# MCU.net
KiCad netlist of a schematic drawn in Altium Designer
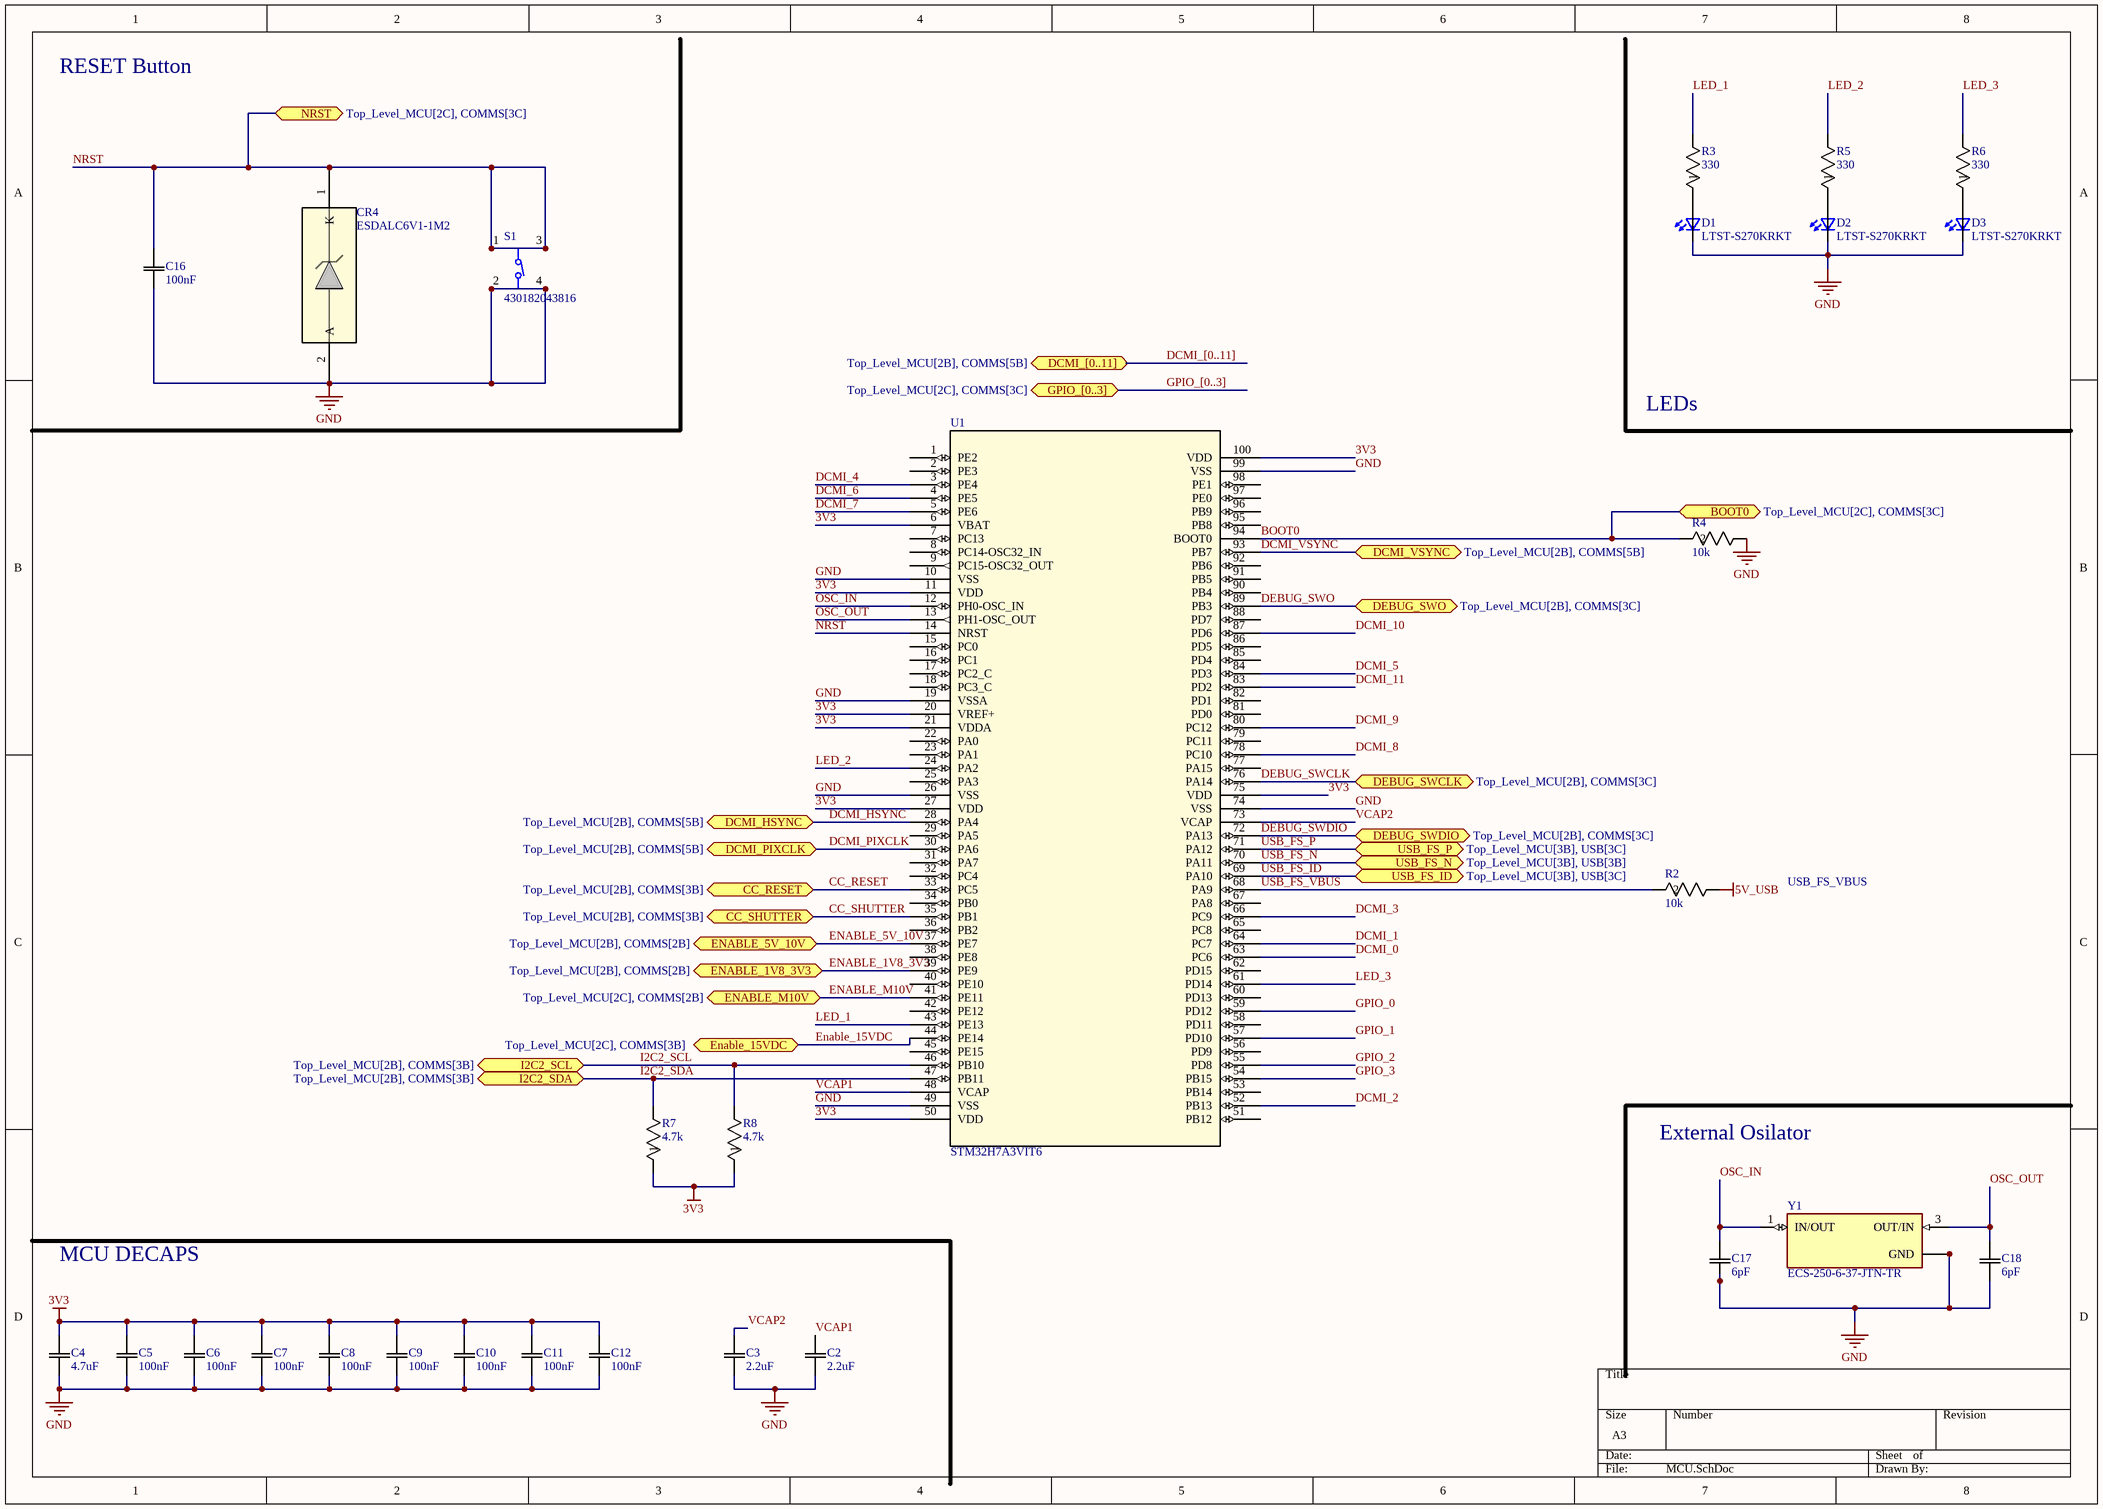
[diagram p0: MCU.SchDoc]

(export (version "E")
  (design (tool "Eeschema 10.0.6"))
  (components
    (comp (ref "C2")
      (value "2.2uF")
      (footprint "CAP_CL10_SAM")
      (description "No Description Available")
      (fields
        (field (name "MANUFACTURER_PART_NUMBER") "CL10B225KP8NNNC")
        (field (name "COPYRIGHT") "Copyright (C) 2025 Ultra Librarian. All rights reserved.")
      )
      (libsource (lib "CL10B225KP8NNNC") (part "CL10B225KP8NNNC"))
    )
    (comp (ref "C3")
      (value "2.2uF")
      (footprint "CAP_CL10_SAM")
      (description "No Description Available")
      (fields
        (field (name "MANUFACTURER_PART_NUMBER") "CL10B225KP8NNNC")
        (field (name "COPYRIGHT") "Copyright (C) 2025 Ultra Librarian. All rights reserved.")
      )
      (libsource (lib "CL10B225KP8NNNC") (part "CL10B225KP8NNNC"))
    )
    (comp (ref "C4")
      (value "4.7uF")
      (footprint "LMK107_TAY")
      (description "No Description Available")
      (fields
        (field (name "MANUFACTURER_PART_NUMBER") "LMK107BJ475MAHT")
        (field (name "COPYRIGHT") "Copyright (C) 2025 Ultra Librarian. All rights reserved.")
      )
      (libsource (lib "LMK107BJ475MAHT") (part "LMK107BJ475MAHT"))
    )
    (comp (ref "C5")
      (value "100nF")
      (footprint "CAPC10555_55N_KEM")
      (description "SMD Comm X7R, Ceramic, 0.1 uF, 10%, 16 VDC, X7R, SMD, MLCC, Temperature Stable, Class II, 0402")
      (fields
        (field (name "MANUFACTURER_PART_NUMBER") "C0402C104K4RACTU")
        (field (name "COPYRIGHT") "Copyright (C) 2025 Ultra Librarian. All rights reserved.")
      )
      (libsource (lib "C0402C104K4RACTU") (part "C0402C104K4RACTU"))
    )
    (comp (ref "C6")
      (value "100nF")
      (footprint "CAPC10555_55N_KEM")
      (description "SMD Comm X7R, Ceramic, 0.1 uF, 10%, 16 VDC, X7R, SMD, MLCC, Temperature Stable, Class II, 0402")
      (fields
        (field (name "MANUFACTURER_PART_NUMBER") "C0402C104K4RACTU")
        (field (name "COPYRIGHT") "Copyright (C) 2025 Ultra Librarian. All rights reserved.")
      )
      (libsource (lib "C0402C104K4RACTU") (part "C0402C104K4RACTU"))
    )
    (comp (ref "C7")
      (value "100nF")
      (footprint "CAPC10555_55N_KEM")
      (description "SMD Comm X7R, Ceramic, 0.1 uF, 10%, 16 VDC, X7R, SMD, MLCC, Temperature Stable, Class II, 0402")
      (fields
        (field (name "MANUFACTURER_PART_NUMBER") "C0402C104K4RACTU")
        (field (name "COPYRIGHT") "Copyright (C) 2025 Ultra Librarian. All rights reserved.")
      )
      (libsource (lib "C0402C104K4RACTU") (part "C0402C104K4RACTU"))
    )
    (comp (ref "C8")
      (value "100nF")
      (footprint "CAPC10555_55N_KEM")
      (description "SMD Comm X7R, Ceramic, 0.1 uF, 10%, 16 VDC, X7R, SMD, MLCC, Temperature Stable, Class II, 0402")
      (fields
        (field (name "MANUFACTURER_PART_NUMBER") "C0402C104K4RACTU")
        (field (name "COPYRIGHT") "Copyright (C) 2025 Ultra Librarian. All rights reserved.")
      )
      (libsource (lib "C0402C104K4RACTU") (part "C0402C104K4RACTU"))
    )
    (comp (ref "C9")
      (value "100nF")
      (footprint "CAPC10555_55N_KEM")
      (description "SMD Comm X7R, Ceramic, 0.1 uF, 10%, 16 VDC, X7R, SMD, MLCC, Temperature Stable, Class II, 0402")
      (fields
        (field (name "MANUFACTURER_PART_NUMBER") "C0402C104K4RACTU")
        (field (name "COPYRIGHT") "Copyright (C) 2025 Ultra Librarian. All rights reserved.")
      )
      (libsource (lib "C0402C104K4RACTU") (part "C0402C104K4RACTU"))
    )
    (comp (ref "C10")
      (value "100nF")
      (footprint "CAPC10555_55N_KEM")
      (description "SMD Comm X7R, Ceramic, 0.1 uF, 10%, 16 VDC, X7R, SMD, MLCC, Temperature Stable, Class II, 0402")
      (fields
        (field (name "MANUFACTURER_PART_NUMBER") "C0402C104K4RACTU")
        (field (name "COPYRIGHT") "Copyright (C) 2025 Ultra Librarian. All rights reserved.")
      )
      (libsource (lib "C0402C104K4RACTU") (part "C0402C104K4RACTU"))
    )
    (comp (ref "C11")
      (value "100nF")
      (footprint "CAPC10555_55N_KEM")
      (description "SMD Comm X7R, Ceramic, 0.1 uF, 10%, 16 VDC, X7R, SMD, MLCC, Temperature Stable, Class II, 0402")
      (fields
        (field (name "MANUFACTURER_PART_NUMBER") "C0402C104K4RACTU")
        (field (name "COPYRIGHT") "Copyright (C) 2025 Ultra Librarian. All rights reserved.")
      )
      (libsource (lib "C0402C104K4RACTU") (part "C0402C104K4RACTU"))
    )
    (comp (ref "C12")
      (value "100nF")
      (footprint "CAPC10555_55N_KEM")
      (description "SMD Comm X7R, Ceramic, 0.1 uF, 10%, 16 VDC, X7R, SMD, MLCC, Temperature Stable, Class II, 0402")
      (fields
        (field (name "MANUFACTURER_PART_NUMBER") "C0402C104K4RACTU")
        (field (name "COPYRIGHT") "Copyright (C) 2025 Ultra Librarian. All rights reserved.")
      )
      (libsource (lib "C0402C104K4RACTU") (part "C0402C104K4RACTU"))
    )
    (comp (ref "C16")
      (value "100nF")
      (footprint "CAPC17595_90N_KEM")
      (description "SMD Comm X5R, Ceramic, 0.1 uF, 10%, 6.3 VDC, X5R, SMD, MLCC, Temperature Stable, Class II, 0603")
      (fields
        (field (name "MANUFACTURER_PART_NUMBER") "C0603C104K9PACTU")
        (field (name "COPYRIGHT") "Copyright (C) 2025 Ultra Librarian. All rights reserved.")
      )
      (libsource (lib "C0603C104K9PACTU") (part "C0603C104K9PACTU"))
    )
    (comp (ref "C17")
      (value "6pF")
      (footprint "CAP_06033D104JAT2A")
      (description "No Description Available")
      (fields
        (field (name "MANUFACTURER_PART_NUMBER") "06035A6R0JAT2A")
        (field (name "COPYRIGHT") "Copyright (C) 2025 Ultra Librarian. All rights reserved.")
      )
      (libsource (lib "06035A6R0JAT2A") (part "06035A6R0JAT2A"))
    )
    (comp (ref "C18")
      (value "6pF")
      (footprint "CAP_06033D104JAT2A")
      (description "No Description Available")
      (fields
        (field (name "MANUFACTURER_PART_NUMBER") "06035A6R0JAT2A")
        (field (name "COPYRIGHT") "Copyright (C) 2025 Ultra Librarian. All rights reserved.")
      )
      (libsource (lib "06035A6R0JAT2A") (part "06035A6R0JAT2A"))
    )
    (comp (ref "CR4")
      (value "ESDALC6V1-1M2")
      (footprint "SOD882_STM")
      (fields (field (name "COPYRIGHT") "Copyright (C) 2025 Ultra Librarian. All rights reserved."))
      (libsource (lib "ESDALC6V1-1M2") (part "ESDALC6V1-1M2"))
    )
    (comp (ref "D1")
      (value "LTST-S270KRKT")
      (footprint "0603")
      (description "http://octopart.com/ltst-c190tbkt-lite-on-550003")
      (fields (field (name "MF") "{'manufacturer': u'Lite-On Inc.'}"))
      (libsource (lib "LTST-S270KRKT") (part "LTST-S270KRKT"))
    )
    (comp (ref "D2")
      (value "LTST-S270KRKT")
      (footprint "0603")
      (description "http://octopart.com/ltst-c190tbkt-lite-on-550003")
      (fields (field (name "MF") "{'manufacturer': u'Lite-On Inc.'}"))
      (libsource (lib "LTST-S270KRKT") (part "LTST-S270KRKT"))
    )
    (comp (ref "D3")
      (value "LTST-S270KRKT")
      (footprint "0603")
      (description "http://octopart.com/ltst-c190tbkt-lite-on-550003")
      (fields (field (name "MF") "{'manufacturer': u'Lite-On Inc.'}"))
      (libsource (lib "LTST-S270KRKT") (part "LTST-S270KRKT"))
    )
    (comp (ref "R2")
      (value "10k")
      (footprint "RC0402N_YAG")
      (description "RES; SMT (0402); 10K; 1%; +/-100PPM/DEGC; 0.0630W")
      (fields
        (field (name "MANUFACTURER_PART_NUMBER") "RC0402FR-0710KL")
        (field (name "COPYRIGHT") "Copyright (C) 2025 Ultra Librarian. All rights reserved.")
      )
      (libsource (lib "RC0402FR-0710KL") (part "RC0402FR-0710KL"))
    )
    (comp (ref "R3")
      (value "330")
      (footprint "STA_RMCF0603_STP")
      (description "No Description Available")
      (fields
        (field (name "MANUFACTURER_PART_NUMBER") "RMCF0603FT330R")
        (field (name "COPYRIGHT") "Copyright (C) 2025 Ultra Librarian. All rights reserved.")
      )
      (libsource (lib "RMCF0603FT330R") (part "RMCF0603FT330R"))
    )
    (comp (ref "R4")
      (value "10k")
      (footprint "RC0402N_YAG")
      (description "RES; SMT (0402); 10K; 1%; +/-100PPM/DEGC; 0.0630W")
      (fields
        (field (name "MANUFACTURER_PART_NUMBER") "RC0402FR-0710KL")
        (field (name "COPYRIGHT") "Copyright (C) 2025 Ultra Librarian. All rights reserved.")
      )
      (libsource (lib "RC0402FR-0710KL") (part "RC0402FR-0710KL"))
    )
    (comp (ref "R5")
      (value "330")
      (footprint "STA_RMCF0603_STP")
      (description "No Description Available")
      (fields
        (field (name "MANUFACTURER_PART_NUMBER") "RMCF0603FT330R")
        (field (name "COPYRIGHT") "Copyright (C) 2025 Ultra Librarian. All rights reserved.")
      )
      (libsource (lib "RMCF0603FT330R") (part "RMCF0603FT330R"))
    )
    (comp (ref "R6")
      (value "330")
      (footprint "STA_RMCF0603_STP")
      (description "No Description Available")
      (fields
        (field (name "MANUFACTURER_PART_NUMBER") "RMCF0603FT330R")
        (field (name "COPYRIGHT") "Copyright (C) 2025 Ultra Librarian. All rights reserved.")
      )
      (libsource (lib "RMCF0603FT330R") (part "RMCF0603FT330R"))
    )
    (comp (ref "R7")
      (value "4.7k")
      (footprint "YAG_R0402_YAG")
      (description "Description")
      (fields
        (field (name "MANUFACTURER_PART_NUMBER") "RC0402FR-074K7L")
        (field (name "COPYRIGHT") "Copyright (C) 2025 Ultra Librarian. All rights reserved.")
      )
      (libsource (lib "RC0402FR-074K7L") (part "RC0402FR-074K7L"))
    )
    (comp (ref "R8")
      (value "4.7k")
      (footprint "YAG_R0402_YAG")
      (description "Description")
      (fields
        (field (name "MANUFACTURER_PART_NUMBER") "RC0402FR-074K7L")
        (field (name "COPYRIGHT") "Copyright (C) 2025 Ultra Librarian. All rights reserved.")
      )
      (libsource (lib "RC0402FR-074K7L") (part "RC0402FR-074K7L"))
    )
    (comp (ref "S1")
      (value "430182043816")
      (footprint "430182043816")
      (description "6*6mm vertical type, SMT, height 4.3mm, black actuator, 160gf, T&R")
      (fields (field (name "MF") "Wurth Electronics"))
      (libsource (lib "430182043816") (part "430182043816"))
    )
    (comp (ref "U1")
      (value "STM32H7A3VIT6")
      (footprint "LQFP100")
      (fields (field (name "COPYRIGHT") "Copyright (C) 2025 Ultra Librarian. All rights reserved."))
      (libsource (lib "STM32H7A3VIT6") (part "STM32H7A3VIT6"))
    )
    (comp (ref "Y1")
      (value "ECS-250-6-37-JTN-TR")
      (footprint "XTAL_ECS-250-6-37-JTN-TR")
      (description "SMD Crystal 2.0 x 1.6 x 0.45 mm ceramic package")
      (libsource (lib "ECS-250-6-37-JTN-TR") (part "ECS-250-6-37-JTN-TR"))
    )
  )
  (nets
    (net (code "1") (name "/BOOT0") (class "Default")
      (node (ref "R4") (pin "2") (pinfunction "2_2") (pintype "passive"))
      (node (ref "U1") (pin "94") (pinfunction "BOOT0_94") (pintype "passive"))
    )
    (net (code "2") (name "/CC_RESET") (class "Default")
      (node (ref "U1") (pin "33") (pinfunction "PC5_33") (pintype "bidirectional"))
    )
    (net (code "3") (name "/CC_SHUTTER") (class "Default")
      (node (ref "U1") (pin "35") (pinfunction "PB1_35") (pintype "bidirectional"))
    )
    (net (code "4") (name "/DCMI_0") (class "Default")
      (node (ref "U1") (pin "63") (pinfunction "PC6_63") (pintype "bidirectional"))
    )
    (net (code "5") (name "/DCMI_1") (class "Default")
      (node (ref "U1") (pin "64") (pinfunction "PC7_64") (pintype "bidirectional"))
    )
    (net (code "6") (name "/DCMI_2") (class "Default")
      (node (ref "U1") (pin "52") (pinfunction "PB13_52") (pintype "bidirectional"))
    )
    (net (code "7") (name "/DCMI_3") (class "Default")
      (node (ref "U1") (pin "66") (pinfunction "PC9_66") (pintype "bidirectional"))
    )
    (net (code "8") (name "/DCMI_4") (class "Default")
      (node (ref "U1") (pin "3") (pinfunction "PE4_3") (pintype "bidirectional"))
    )
    (net (code "9") (name "/DCMI_5") (class "Default")
      (node (ref "U1") (pin "84") (pinfunction "PD3_84") (pintype "bidirectional"))
    )
    (net (code "10") (name "/DCMI_6") (class "Default")
      (node (ref "U1") (pin "4") (pinfunction "PE5_4") (pintype "bidirectional"))
    )
    (net (code "11") (name "/DCMI_7") (class "Default")
      (node (ref "U1") (pin "5") (pinfunction "PE6_5") (pintype "bidirectional"))
    )
    (net (code "12") (name "/DCMI_8") (class "Default")
      (node (ref "U1") (pin "78") (pinfunction "PC10_78") (pintype "bidirectional"))
    )
    (net (code "13") (name "/DCMI_9") (class "Default")
      (node (ref "U1") (pin "80") (pinfunction "PC12_80") (pintype "bidirectional"))
    )
    (net (code "14") (name "/DCMI_10") (class "Default")
      (node (ref "U1") (pin "87") (pinfunction "PD6_87") (pintype "bidirectional"))
    )
    (net (code "15") (name "/DCMI_11") (class "Default")
      (node (ref "U1") (pin "83") (pinfunction "PD2_83") (pintype "bidirectional"))
    )
    (net (code "16") (name "/DCMI_HSYNC") (class "Default")
      (node (ref "U1") (pin "28") (pinfunction "PA4_28") (pintype "bidirectional"))
    )
    (net (code "17") (name "/DCMI_PIXCLK") (class "Default")
      (node (ref "U1") (pin "30") (pinfunction "PA6_30") (pintype "bidirectional"))
    )
    (net (code "18") (name "/DCMI_VSYNC") (class "Default")
      (node (ref "U1") (pin "93") (pinfunction "PB7_93") (pintype "bidirectional"))
    )
    (net (code "20") (name "/DEBUG_SWCLK") (class "Default")
      (node (ref "U1") (pin "76") (pinfunction "PA14_76") (pintype "bidirectional"))
    )
    (net (code "21") (name "/DEBUG_SWDIO") (class "Default")
      (node (ref "U1") (pin "72") (pinfunction "PA13_72") (pintype "bidirectional"))
    )
    (net (code "22") (name "/DEBUG_SWO") (class "Default")
      (node (ref "U1") (pin "89") (pinfunction "PB3_89") (pintype "bidirectional"))
    )
    (net (code "23") (name "/ENABLE_1V8_3V3") (class "Default")
      (node (ref "U1") (pin "39") (pinfunction "PE9_39") (pintype "bidirectional"))
    )
    (net (code "24") (name "/ENABLE_5V_10V") (class "Default")
      (node (ref "U1") (pin "37") (pinfunction "PE7_37") (pintype "bidirectional"))
    )
    (net (code "25") (name "/ENABLE_M10V") (class "Default")
      (node (ref "U1") (pin "41") (pinfunction "PE11_41") (pintype "bidirectional"))
    )
    (net (code "26") (name "/Enable_15VDC") (class "Default")
      (node (ref "U1") (pin "44") (pinfunction "PE14_44") (pintype "bidirectional"))
    )
    (net (code "27") (name "/GPIO_0") (class "Default")
      (node (ref "U1") (pin "59") (pinfunction "PD12_59") (pintype "bidirectional"))
    )
    (net (code "28") (name "/GPIO_1") (class "Default")
      (node (ref "U1") (pin "57") (pinfunction "PD10_57") (pintype "bidirectional"))
    )
    (net (code "29") (name "/GPIO_2") (class "Default")
      (node (ref "U1") (pin "55") (pinfunction "PD8_55") (pintype "bidirectional"))
    )
    (net (code "30") (name "/GPIO_3") (class "Default")
      (node (ref "U1") (pin "54") (pinfunction "PB15_54") (pintype "bidirectional"))
    )
    (net (code "32") (name "/I2C2_SCL") (class "Default")
      (node (ref "R8") (pin "2") (pinfunction "2_2") (pintype "passive"))
      (node (ref "U1") (pin "46") (pinfunction "PB10_46") (pintype "bidirectional"))
    )
    (net (code "33") (name "/I2C2_SDA") (class "Default")
      (node (ref "R7") (pin "2") (pinfunction "2_2") (pintype "passive"))
      (node (ref "U1") (pin "47") (pinfunction "PB11_47") (pintype "bidirectional"))
    )
    (net (code "34") (name "/LED_1") (class "Default")
      (node (ref "R3") (pin "2") (pinfunction "2_2") (pintype "passive"))
      (node (ref "U1") (pin "43") (pinfunction "PE13_43") (pintype "bidirectional"))
    )
    (net (code "35") (name "/LED_2") (class "Default")
      (node (ref "R5") (pin "2") (pinfunction "2_2") (pintype "passive"))
      (node (ref "U1") (pin "24") (pinfunction "PA2_24") (pintype "bidirectional"))
    )
    (net (code "36") (name "/LED_3") (class "Default")
      (node (ref "R6") (pin "2") (pinfunction "2_2") (pintype "passive"))
      (node (ref "U1") (pin "61") (pinfunction "PD14_61") (pintype "bidirectional"))
    )
    (net (code "37") (name "/NRST") (class "Default")
      (node (ref "C16") (pin "2") (pinfunction "2_2") (pintype "passive"))
      (node (ref "CR4") (pin "1") (pinfunction "K_1") (pintype "passive"))
      (node (ref "S1") (pin "1") (pinfunction "1_1") (pintype "passive"))
      (node (ref "S1") (pin "3") (pinfunction "3_3") (pintype "passive"))
      (node (ref "U1") (pin "14") (pinfunction "NRST_14") (pintype "passive"))
    )
    (net (code "38") (name "/OSC_IN") (class "Default")
      (node (ref "C17") (pin "2") (pinfunction "EPAD_2") (pintype "passive"))
      (node (ref "U1") (pin "12") (pinfunction "PH0-OSC_IN_12") (pintype "bidirectional"))
      (node (ref "Y1") (pin "1") (pinfunction "IN/OUT_1") (pintype "bidirectional"))
    )
    (net (code "39") (name "/OSC_OUT") (class "Default")
      (node (ref "C18") (pin "2") (pinfunction "EPAD_2") (pintype "passive"))
      (node (ref "U1") (pin "13") (pinfunction "PH1-OSC_OUT_13") (pintype "output"))
      (node (ref "Y1") (pin "3") (pinfunction "OUT/IN_3") (pintype "input"))
    )
    (net (code "40") (name "/USB_FS_ID") (class "Default")
      (node (ref "U1") (pin "69") (pinfunction "PA10_69") (pintype "bidirectional"))
    )
    (net (code "41") (name "/USB_FS_N") (class "Default")
      (node (ref "U1") (pin "70") (pinfunction "PA11_70") (pintype "bidirectional"))
    )
    (net (code "42") (name "/USB_FS_P") (class "Default")
      (node (ref "U1") (pin "71") (pinfunction "PA12_71") (pintype "bidirectional"))
    )
    (net (code "43") (name "/USB_FS_VBUS") (class "Default")
      (node (ref "R2") (pin "2") (pinfunction "2_2") (pintype "passive"))
      (node (ref "U1") (pin "68") (pinfunction "PA9_68") (pintype "bidirectional"))
    )
    (net (code "44") (name "/VCAP1") (class "Default")
      (node (ref "C2") (pin "2") (pinfunction "2_2") (pintype "passive"))
      (node (ref "U1") (pin "48") (pinfunction "VCAP_48") (pintype "passive"))
    )
    (net (code "45") (name "/VCAP2") (class "Default")
      (node (ref "C3") (pin "2") (pinfunction "2_2") (pintype "passive"))
      (node (ref "U1") (pin "73") (pinfunction "VCAP_73") (pintype "passive"))
    )
    (net (code "46") (name "3V3") (class "Default")
      (node (ref "C10") (pin "2") (pinfunction "2_2") (pintype "passive"))
      (node (ref "C11") (pin "2") (pinfunction "2_2") (pintype "passive"))
      (node (ref "C12") (pin "2") (pinfunction "2_2") (pintype "passive"))
      (node (ref "C4") (pin "2") (pinfunction "2_2") (pintype "passive"))
      (node (ref "C5") (pin "2") (pinfunction "2_2") (pintype "passive"))
      (node (ref "C6") (pin "2") (pinfunction "2_2") (pintype "passive"))
      (node (ref "C7") (pin "2") (pinfunction "2_2") (pintype "passive"))
      (node (ref "C8") (pin "2") (pinfunction "2_2") (pintype "passive"))
      (node (ref "C9") (pin "2") (pinfunction "2_2") (pintype "passive"))
      (node (ref "R7") (pin "1") (pinfunction "1_1") (pintype "passive"))
      (node (ref "R8") (pin "1") (pinfunction "1_1") (pintype "passive"))
      (node (ref "U1") (pin "100") (pinfunction "VDD_100") (pintype "power_in"))
      (node (ref "U1") (pin "11") (pinfunction "VDD_11") (pintype "power_in"))
      (node (ref "U1") (pin "20") (pinfunction "VREF+_20") (pintype "power_in"))
      (node (ref "U1") (pin "21") (pinfunction "VDDA_21") (pintype "power_in"))
      (node (ref "U1") (pin "27") (pinfunction "VDD_27") (pintype "power_in"))
      (node (ref "U1") (pin "50") (pinfunction "VDD_50") (pintype "power_in"))
      (node (ref "U1") (pin "6") (pinfunction "VBAT_6") (pintype "passive"))
      (node (ref "U1") (pin "75") (pinfunction "VDD_75") (pintype "power_in"))
    )
    (net (code "47") (name "5V_USB") (class "Default")
      (node (ref "R2") (pin "1") (pinfunction "1_1") (pintype "passive"))
    )
    (net (code "48") (name "GND") (class "Default")
      (node (ref "C10") (pin "1") (pinfunction "1_1") (pintype "passive"))
      (node (ref "C11") (pin "1") (pinfunction "1_1") (pintype "passive"))
      (node (ref "C12") (pin "1") (pinfunction "1_1") (pintype "passive"))
      (node (ref "C16") (pin "1") (pinfunction "1_1") (pintype "passive"))
      (node (ref "C17") (pin "1") (pinfunction "EPAD_1") (pintype "passive"))
      (node (ref "C18") (pin "1") (pinfunction "EPAD_1") (pintype "passive"))
      (node (ref "C2") (pin "1") (pinfunction "1_1") (pintype "passive"))
      (node (ref "C3") (pin "1") (pinfunction "1_1") (pintype "passive"))
      (node (ref "C4") (pin "1") (pinfunction "1_1") (pintype "passive"))
      (node (ref "C5") (pin "1") (pinfunction "1_1") (pintype "passive"))
      (node (ref "C6") (pin "1") (pinfunction "1_1") (pintype "passive"))
      (node (ref "C7") (pin "1") (pinfunction "1_1") (pintype "passive"))
      (node (ref "C8") (pin "1") (pinfunction "1_1") (pintype "passive"))
      (node (ref "C9") (pin "1") (pinfunction "1_1") (pintype "passive"))
      (node (ref "CR4") (pin "2") (pinfunction "A_2") (pintype "passive"))
      (node (ref "D1") (pin "1") (pinfunction "K2_1") (pintype "passive"))
      (node (ref "D2") (pin "1") (pinfunction "K2_1") (pintype "passive"))
      (node (ref "D3") (pin "1") (pinfunction "K2_1") (pintype "passive"))
      (node (ref "R4") (pin "1") (pinfunction "1_1") (pintype "passive"))
      (node (ref "S1") (pin "2") (pinfunction "2_2") (pintype "passive"))
      (node (ref "S1") (pin "4") (pinfunction "4_4") (pintype "passive"))
      (node (ref "U1") (pin "10") (pinfunction "VSS_10") (pintype "power_in"))
      (node (ref "U1") (pin "19") (pinfunction "VSSA_19") (pintype "power_in"))
      (node (ref "U1") (pin "26") (pinfunction "VSS_26") (pintype "power_in"))
      (node (ref "U1") (pin "49") (pinfunction "VSS_49") (pintype "power_in"))
      (node (ref "U1") (pin "74") (pinfunction "VSS_74") (pintype "power_in"))
      (node (ref "U1") (pin "99") (pinfunction "VSS_99") (pintype "power_in"))
      (node (ref "Y1") (pin "2") (pinfunction "GND_2") (pintype "power_in"))
      (node (ref "Y1") (pin "4") (pinfunction "GND_4") (pintype "power_in"))
    )
    (net (code "49") (name "Net-(D1-A2)") (class "Default")
      (node (ref "D1") (pin "2") (pinfunction "A2_2") (pintype "passive"))
      (node (ref "R3") (pin "1") (pinfunction "1_1") (pintype "passive"))
    )
    (net (code "50") (name "Net-(D2-A2)") (class "Default")
      (node (ref "D2") (pin "2") (pinfunction "A2_2") (pintype "passive"))
      (node (ref "R5") (pin "1") (pinfunction "1_1") (pintype "passive"))
    )
    (net (code "51") (name "Net-(D3-A2)") (class "Default")
      (node (ref "D3") (pin "2") (pinfunction "A2_2") (pintype "passive"))
      (node (ref "R6") (pin "1") (pinfunction "1_1") (pintype "passive"))
    )
    (net (code "52") (name "unconnected-(U1-PA0-Pad22)") (class "Default")
      (node (ref "U1") (pin "22") (pinfunction "PA0_22") (pintype "bidirectional"))
    )
    (net (code "53") (name "unconnected-(U1-PA1-Pad23)") (class "Default")
      (node (ref "U1") (pin "23") (pinfunction "PA1_23") (pintype "bidirectional"))
    )
    (net (code "54") (name "unconnected-(U1-PA3-Pad25)") (class "Default")
      (node (ref "U1") (pin "25") (pinfunction "PA3_25") (pintype "bidirectional"))
    )
    (net (code "55") (name "unconnected-(U1-PA5-Pad29)") (class "Default")
      (node (ref "U1") (pin "29") (pinfunction "PA5_29") (pintype "bidirectional"))
    )
    (net (code "56") (name "unconnected-(U1-PA7-Pad31)") (class "Default")
      (node (ref "U1") (pin "31") (pinfunction "PA7_31") (pintype "bidirectional"))
    )
    (net (code "57") (name "unconnected-(U1-PA8-Pad67)") (class "Default")
      (node (ref "U1") (pin "67") (pinfunction "PA8_67") (pintype "bidirectional"))
    )
    (net (code "58") (name "unconnected-(U1-PA15-Pad77)") (class "Default")
      (node (ref "U1") (pin "77") (pinfunction "PA15_77") (pintype "bidirectional"))
    )
    (net (code "59") (name "unconnected-(U1-PB0-Pad34)") (class "Default")
      (node (ref "U1") (pin "34") (pinfunction "PB0_34") (pintype "bidirectional"))
    )
    (net (code "60") (name "unconnected-(U1-PB2-Pad36)") (class "Default")
      (node (ref "U1") (pin "36") (pinfunction "PB2_36") (pintype "bidirectional"))
    )
    (net (code "61") (name "unconnected-(U1-PB4-Pad90)") (class "Default")
      (node (ref "U1") (pin "90") (pinfunction "PB4_90") (pintype "bidirectional"))
    )
    (net (code "62") (name "unconnected-(U1-PB5-Pad91)") (class "Default")
      (node (ref "U1") (pin "91") (pinfunction "PB5_91") (pintype "bidirectional"))
    )
    (net (code "63") (name "unconnected-(U1-PB6-Pad92)") (class "Default")
      (node (ref "U1") (pin "92") (pinfunction "PB6_92") (pintype "bidirectional"))
    )
    (net (code "64") (name "unconnected-(U1-PB8-Pad95)") (class "Default")
      (node (ref "U1") (pin "95") (pinfunction "PB8_95") (pintype "bidirectional"))
    )
    (net (code "65") (name "unconnected-(U1-PB9-Pad96)") (class "Default")
      (node (ref "U1") (pin "96") (pinfunction "PB9_96") (pintype "bidirectional"))
    )
    (net (code "66") (name "unconnected-(U1-PB12-Pad51)") (class "Default")
      (node (ref "U1") (pin "51") (pinfunction "PB12_51") (pintype "bidirectional"))
    )
    (net (code "67") (name "unconnected-(U1-PB14-Pad53)") (class "Default")
      (node (ref "U1") (pin "53") (pinfunction "PB14_53") (pintype "bidirectional"))
    )
    (net (code "68") (name "unconnected-(U1-PC0-Pad15)") (class "Default")
      (node (ref "U1") (pin "15") (pinfunction "PC0_15") (pintype "bidirectional"))
    )
    (net (code "69") (name "unconnected-(U1-PC1-Pad16)") (class "Default")
      (node (ref "U1") (pin "16") (pinfunction "PC1_16") (pintype "bidirectional"))
    )
    (net (code "70") (name "unconnected-(U1-PC2_C-Pad17)") (class "Default")
      (node (ref "U1") (pin "17") (pinfunction "PC2_C_17") (pintype "bidirectional"))
    )
    (net (code "71") (name "unconnected-(U1-PC3_C-Pad18)") (class "Default")
      (node (ref "U1") (pin "18") (pinfunction "PC3_C_18") (pintype "bidirectional"))
    )
    (net (code "72") (name "unconnected-(U1-PC4-Pad32)") (class "Default")
      (node (ref "U1") (pin "32") (pinfunction "PC4_32") (pintype "bidirectional"))
    )
    (net (code "73") (name "unconnected-(U1-PC8-Pad65)") (class "Default")
      (node (ref "U1") (pin "65") (pinfunction "PC8_65") (pintype "bidirectional"))
    )
    (net (code "74") (name "unconnected-(U1-PC11-Pad79)") (class "Default")
      (node (ref "U1") (pin "79") (pinfunction "PC11_79") (pintype "bidirectional"))
    )
    (net (code "75") (name "unconnected-(U1-PC13-Pad7)") (class "Default")
      (node (ref "U1") (pin "7") (pinfunction "PC13_7") (pintype "bidirectional"))
    )
    (net (code "76") (name "unconnected-(U1-PC14-OSC32_IN-Pad8)") (class "Default")
      (node (ref "U1") (pin "8") (pinfunction "PC14-OSC32_IN_8") (pintype "bidirectional"))
    )
    (net (code "77") (name "unconnected-(U1-PC15-OSC32_OUT-Pad9)") (class "Default")
      (node (ref "U1") (pin "9") (pinfunction "PC15-OSC32_OUT_9") (pintype "output"))
    )
    (net (code "78") (name "unconnected-(U1-PD0-Pad81)") (class "Default")
      (node (ref "U1") (pin "81") (pinfunction "PD0_81") (pintype "bidirectional"))
    )
    (net (code "79") (name "unconnected-(U1-PD1-Pad82)") (class "Default")
      (node (ref "U1") (pin "82") (pinfunction "PD1_82") (pintype "bidirectional"))
    )
    (net (code "80") (name "unconnected-(U1-PD4-Pad85)") (class "Default")
      (node (ref "U1") (pin "85") (pinfunction "PD4_85") (pintype "bidirectional"))
    )
    (net (code "81") (name "unconnected-(U1-PD5-Pad86)") (class "Default")
      (node (ref "U1") (pin "86") (pinfunction "PD5_86") (pintype "bidirectional"))
    )
    (net (code "82") (name "unconnected-(U1-PD7-Pad88)") (class "Default")
      (node (ref "U1") (pin "88") (pinfunction "PD7_88") (pintype "bidirectional"))
    )
    (net (code "83") (name "unconnected-(U1-PD9-Pad56)") (class "Default")
      (node (ref "U1") (pin "56") (pinfunction "PD9_56") (pintype "bidirectional"))
    )
    (net (code "84") (name "unconnected-(U1-PD11-Pad58)") (class "Default")
      (node (ref "U1") (pin "58") (pinfunction "PD11_58") (pintype "bidirectional"))
    )
    (net (code "85") (name "unconnected-(U1-PD13-Pad60)") (class "Default")
      (node (ref "U1") (pin "60") (pinfunction "PD13_60") (pintype "bidirectional"))
    )
    (net (code "86") (name "unconnected-(U1-PD15-Pad62)") (class "Default")
      (node (ref "U1") (pin "62") (pinfunction "PD15_62") (pintype "bidirectional"))
    )
    (net (code "87") (name "unconnected-(U1-PE0-Pad97)") (class "Default")
      (node (ref "U1") (pin "97") (pinfunction "PE0_97") (pintype "bidirectional"))
    )
    (net (code "88") (name "unconnected-(U1-PE1-Pad98)") (class "Default")
      (node (ref "U1") (pin "98") (pinfunction "PE1_98") (pintype "bidirectional"))
    )
    (net (code "89") (name "unconnected-(U1-PE2-Pad1)") (class "Default")
      (node (ref "U1") (pin "1") (pinfunction "PE2_1") (pintype "bidirectional"))
    )
    (net (code "90") (name "unconnected-(U1-PE3-Pad2)") (class "Default")
      (node (ref "U1") (pin "2") (pinfunction "PE3_2") (pintype "bidirectional"))
    )
    (net (code "91") (name "unconnected-(U1-PE8-Pad38)") (class "Default")
      (node (ref "U1") (pin "38") (pinfunction "PE8_38") (pintype "bidirectional"))
    )
    (net (code "92") (name "unconnected-(U1-PE10-Pad40)") (class "Default")
      (node (ref "U1") (pin "40") (pinfunction "PE10_40") (pintype "bidirectional"))
    )
    (net (code "93") (name "unconnected-(U1-PE12-Pad42)") (class "Default")
      (node (ref "U1") (pin "42") (pinfunction "PE12_42") (pintype "bidirectional"))
    )
    (net (code "94") (name "unconnected-(U1-PE15-Pad45)") (class "Default")
      (node (ref "U1") (pin "45") (pinfunction "PE15_45") (pintype "bidirectional"))
    )
  )
)
